# caretaker-easyvr.net
KiCad netlist of a schematic drawn in EAGLE
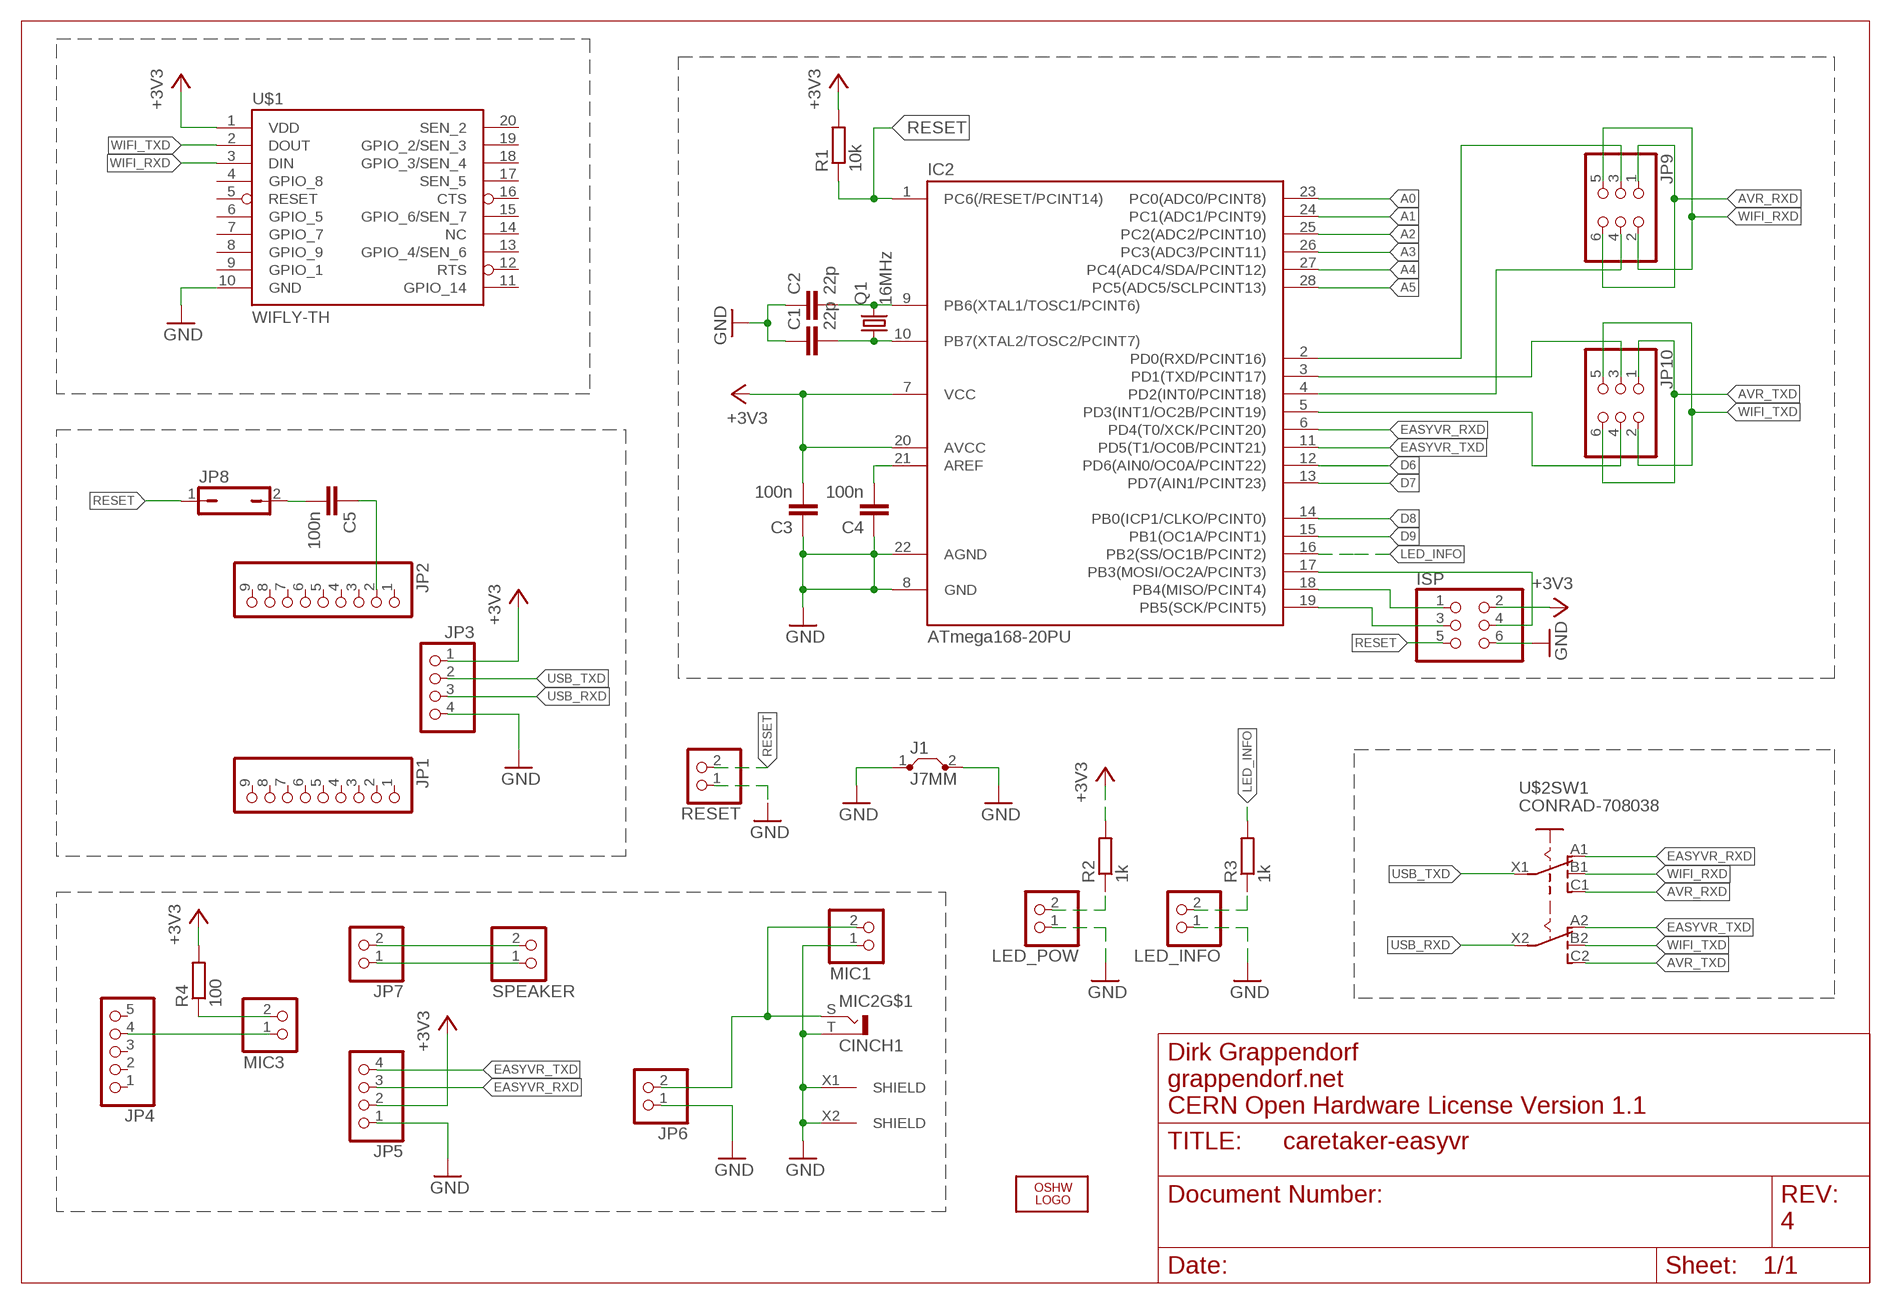
[diagram p0: schematic, sheet 1]

(export (version "E")
  (design (tool "Eeschema 10.0.6"))
  (components
    (comp (ref "C1")
      (value "22p")
      (footprint "eagle-import:C025-025X050")
      (libsource (lib "eagle-import") (part "C-EU025-025X050"))
    )
    (comp (ref "C2")
      (value "22p")
      (footprint "eagle-import:C025-025X050")
      (libsource (lib "eagle-import") (part "C-EU025-025X050"))
    )
    (comp (ref "C3")
      (value "100n")
      (footprint "eagle-import:C025-024X044")
      (libsource (lib "eagle-import") (part "C-EU025-024X044"))
    )
    (comp (ref "C4")
      (value "100n")
      (footprint "eagle-import:C025-024X044")
      (libsource (lib "eagle-import") (part "C-EU025-024X044"))
    )
    (comp (ref "C5")
      (value "100n")
      (footprint "eagle-import:C025-024X044")
      (libsource (lib "eagle-import") (part "C-EU025-024X044"))
    )
    (comp (ref "IC2")
      (value "ATmega168-20PU")
      (footprint "eagle-import:DIL28-3")
      (libsource (lib "eagle-import") (part "ATMEGA48/88/168-PU"))
    )
    (comp (ref "ISP")
      (value "PINHD-2X3")
      (footprint "eagle-import:2X03")
      (libsource (lib "eagle-import") (part "PINHD-2X3"))
    )
    (comp (ref "J1")
      (value "J7MM")
      (footprint "eagle-import:07")
      (libsource (lib "eagle-import") (part "J7MM"))
    )
    (comp (ref "JP1")
      (value "PINHD-1X9")
      (footprint "eagle-import:1X09")
      (libsource (lib "eagle-import") (part "PINHD-1X9"))
    )
    (comp (ref "JP2")
      (value "PINHD-1X9")
      (footprint "eagle-import:1X09")
      (libsource (lib "eagle-import") (part "PINHD-1X9"))
    )
    (comp (ref "JP3")
      (value "PINHD-1X4")
      (footprint "eagle-import:1X04")
      (libsource (lib "eagle-import") (part "PINHD-1X4"))
    )
    (comp (ref "JP4")
      (value "PINHD-1X5_2.00")
      (footprint "eagle-import:1X05M")
      (libsource (lib "eagle-import") (part "PINHD-1X5_2.00"))
    )
    (comp (ref "JP5")
      (value "PINHD-1X4_2.00")
      (footprint "eagle-import:1X04M")
      (libsource (lib "eagle-import") (part "PINHD-1X4_2.00"))
    )
    (comp (ref "JP6")
      (value "PINHD-1X2_2.00")
      (footprint "eagle-import:1X02M")
      (libsource (lib "eagle-import") (part "PINHD-1X2_2.00"))
    )
    (comp (ref "JP7")
      (value "PINHD-1X2_2.00")
      (footprint "eagle-import:1X02M")
      (libsource (lib "eagle-import") (part "PINHD-1X2_2.00"))
    )
    (comp (ref "JP8")
      (value "JP1Q")
      (footprint "eagle-import:JP1")
      (libsource (lib "eagle-import") (part "JP1Q"))
    )
    (comp (ref "JP9")
      (value "PINHD-2X3_2.54")
      (footprint "eagle-import:2X03")
      (libsource (lib "eagle-import") (part "PINHD-2X3_2.54"))
    )
    (comp (ref "JP10")
      (value "PINHD-2X3_2.54")
      (footprint "eagle-import:2X03")
      (libsource (lib "eagle-import") (part "PINHD-2X3_2.54"))
    )
    (comp (ref "LED_INFO")
      (value "PINHD-1X2_2.54")
      (footprint "eagle-import:1X02")
      (libsource (lib "eagle-import") (part "PINHD-1X2_2.54"))
    )
    (comp (ref "LED_POW")
      (value "PINHD-1X2_2.54")
      (footprint "eagle-import:1X02")
      (libsource (lib "eagle-import") (part "PINHD-1X2_2.54"))
    )
    (comp (ref "LOGO2")
      (value "OSHW_LOGO_10MILX0350-NT-BOTTOM")
      (footprint "eagle-import:OSHW_10X350_NOTEXT_BOTTOM")
      (libsource (lib "eagle-import") (part "OSHW_LOGO_10MILX0350-NT-BOTTOM"))
    )
    (comp (ref "MIC1")
      (value "PINHD-1X2_2.54")
      (footprint "eagle-import:1X02")
      (libsource (lib "eagle-import") (part "PINHD-1X2_2.54"))
    )
    (comp (ref "MIC2")
      (value "CINCH1")
      (footprint "eagle-import:CINCH1")
      (libsource (lib "eagle-import") (part "CINCH1"))
    )
    (comp (ref "MIC3")
      (value "PINHD-1X2_2.54")
      (footprint "eagle-import:1X02")
      (libsource (lib "eagle-import") (part "PINHD-1X2_2.54"))
    )
    (comp (ref "Q1")
      (value "16MHz")
      (footprint "eagle-import:HC49U-V")
      (libsource (lib "eagle-import") (part "CRYSTALHC49U-V"))
    )
    (comp (ref "R1")
      (value "10k")
      (footprint "eagle-import:0204_7")
      (libsource (lib "eagle-import") (part "R-EU_0204/7"))
    )
    (comp (ref "R2")
      (value "1k")
      (footprint "eagle-import:0204_7")
      (libsource (lib "eagle-import") (part "R-EU_0204/7"))
    )
    (comp (ref "R3")
      (value "1k")
      (footprint "eagle-import:0204_7")
      (libsource (lib "eagle-import") (part "R-EU_0204/7"))
    )
    (comp (ref "R4")
      (value "100")
      (footprint "eagle-import:0204_7")
      (libsource (lib "eagle-import") (part "R-EU_0204/7"))
    )
    (comp (ref "RESET")
      (value "PINHD-1X2_2.54")
      (footprint "eagle-import:1X02")
      (libsource (lib "eagle-import") (part "PINHD-1X2_2.54"))
    )
    (comp (ref "SPEAKER")
      (value "PINHD-1X2_2.54")
      (footprint "eagle-import:1X02")
      (libsource (lib "eagle-import") (part "PINHD-1X2_2.54"))
    )
    (comp (ref "U$1")
      (value "WIFLY-TH")
      (footprint "eagle-import:WIFLY-TH")
      (libsource (lib "eagle-import") (part "WIFLY-TH"))
    )
    (comp (ref "U$2")
      (value "CONRAD-708038")
      (footprint "eagle-import:CONRAD-708038")
      (libsource (lib "eagle-import") (part "CONRAD-708038"))
    )
  )
  (nets
    (net (code "1") (name "+3V3") (class "Default")
      (node (ref "C3") (pin "2") (pinfunction "2_2") (pintype "passive"))
      (node (ref "IC2") (pin "20") (pinfunction "AVCC_20") (pintype "passive"))
      (node (ref "IC2") (pin "7") (pinfunction "VCC_7") (pintype "power_in"))
      (node (ref "ISP") (pin "2") (pinfunction "2_2") (pintype "passive"))
      (node (ref "JP3") (pin "1") (pinfunction "1_1") (pintype "passive"))
      (node (ref "JP5") (pin "2") (pinfunction "2_2") (pintype "passive"))
      (node (ref "R1") (pin "2") (pinfunction "2_2") (pintype "passive"))
      (node (ref "R2") (pin "2") (pinfunction "2_2") (pintype "passive"))
      (node (ref "R4") (pin "2") (pinfunction "2_2") (pintype "passive"))
      (node (ref "U$1") (pin "1") (pinfunction "VDD_1") (pintype "power_in"))
    )
    (net (code "2") (name "A0") (class "Default")
      (node (ref "IC2") (pin "23") (pinfunction "PC0(ADC0/PCINT8)_23") (pintype "bidirectional"))
    )
    (net (code "3") (name "A1") (class "Default")
      (node (ref "IC2") (pin "24") (pinfunction "PC1(ADC1/PCINT9)_24") (pintype "bidirectional"))
    )
    (net (code "4") (name "A2") (class "Default")
      (node (ref "IC2") (pin "25") (pinfunction "PC2(ADC2/PCINT10)_25") (pintype "bidirectional"))
    )
    (net (code "5") (name "A3") (class "Default")
      (node (ref "IC2") (pin "26") (pinfunction "PC3(ADC3/PCINT11)_26") (pintype "bidirectional"))
    )
    (net (code "6") (name "A4") (class "Default")
      (node (ref "IC2") (pin "27") (pinfunction "PC4(ADC4/SDA/PCINT12)_27") (pintype "bidirectional"))
    )
    (net (code "7") (name "A5") (class "Default")
      (node (ref "IC2") (pin "28") (pinfunction "PC5(ADC5/SCLPCINT13)_28") (pintype "bidirectional"))
    )
    (net (code "8") (name "AVR_RXD") (class "Default")
      (node (ref "JP9") (pin "1") (pinfunction "1_1") (pintype "passive"))
      (node (ref "JP9") (pin "6") (pinfunction "6_6") (pintype "passive"))
      (node (ref "U$2") (pin "C1") (pinfunction "C1_C1") (pintype "bidirectional"))
    )
    (net (code "9") (name "AVR_TXD") (class "Default")
      (node (ref "JP10") (pin "1") (pinfunction "1_1") (pintype "passive"))
      (node (ref "JP10") (pin "6") (pinfunction "6_6") (pintype "passive"))
      (node (ref "U$2") (pin "C2") (pinfunction "C2_C2") (pintype "bidirectional"))
    )
    (net (code "10") (name "D6") (class "Default")
      (node (ref "IC2") (pin "12") (pinfunction "PD6(AIN0/OC0A/PCINT22)_12") (pintype "bidirectional"))
    )
    (net (code "11") (name "D7") (class "Default")
      (node (ref "IC2") (pin "13") (pinfunction "PD7(AIN1/PCINT23)_13") (pintype "bidirectional"))
    )
    (net (code "12") (name "D8") (class "Default")
      (node (ref "IC2") (pin "14") (pinfunction "PB0(ICP1/CLKO/PCINT0)_14") (pintype "bidirectional"))
    )
    (net (code "13") (name "D9") (class "Default")
      (node (ref "IC2") (pin "15") (pinfunction "PB1(OC1A/PCINT1)_15") (pintype "bidirectional"))
    )
    (net (code "14") (name "EASYVR_RXD") (class "Default")
      (node (ref "IC2") (pin "6") (pinfunction "PD4(T0/XCK/PCINT20)_6") (pintype "bidirectional"))
      (node (ref "JP5") (pin "3") (pinfunction "3_3") (pintype "passive"))
      (node (ref "U$2") (pin "A1") (pinfunction "A1_A1") (pintype "bidirectional"))
    )
    (net (code "15") (name "EASYVR_TXD") (class "Default")
      (node (ref "IC2") (pin "11") (pinfunction "PD5(T1/OC0B/PCINT21)_11") (pintype "bidirectional"))
      (node (ref "JP5") (pin "4") (pinfunction "4_4") (pintype "passive"))
      (node (ref "U$2") (pin "A2") (pinfunction "A2_A2") (pintype "bidirectional"))
    )
    (net (code "16") (name "GND") (class "Default")
      (node (ref "C1") (pin "1") (pinfunction "1_1") (pintype "passive"))
      (node (ref "C2") (pin "1") (pinfunction "1_1") (pintype "passive"))
      (node (ref "C3") (pin "1") (pinfunction "1_1") (pintype "passive"))
      (node (ref "C4") (pin "1") (pinfunction "1_1") (pintype "passive"))
      (node (ref "IC2") (pin "22") (pinfunction "AGND_22") (pintype "power_in"))
      (node (ref "IC2") (pin "8") (pinfunction "GND_8") (pintype "power_in"))
      (node (ref "ISP") (pin "6") (pinfunction "6_6") (pintype "passive"))
      (node (ref "J1") (pin "1") (pinfunction "1_1") (pintype "passive"))
      (node (ref "J1") (pin "2") (pinfunction "2_2") (pintype "passive"))
      (node (ref "JP3") (pin "4") (pinfunction "4_4") (pintype "passive"))
      (node (ref "JP5") (pin "1") (pinfunction "1_1") (pintype "passive"))
      (node (ref "JP6") (pin "1") (pinfunction "1_1") (pintype "passive"))
      (node (ref "LED_INFO") (pin "1") (pinfunction "1_1") (pintype "passive"))
      (node (ref "LED_POW") (pin "1") (pinfunction "1_1") (pintype "passive"))
      (node (ref "MIC1") (pin "1") (pinfunction "1_1") (pintype "passive"))
      (node (ref "MIC2") (pin "T") (pinfunction "T_T") (pintype "passive"))
      (node (ref "MIC2") (pin "X1") (pinfunction "SHIELD_X1") (pintype "power_in"))
      (node (ref "MIC2") (pin "X2") (pinfunction "SHIELD_X2") (pintype "power_in"))
      (node (ref "RESET") (pin "1") (pinfunction "1_1") (pintype "passive"))
      (node (ref "U$1") (pin "10") (pinfunction "GND_10") (pintype "power_in"))
    )
    (net (code "17") (name "LED_INFO") (class "Default")
      (node (ref "IC2") (pin "16") (pinfunction "PB2(SS/OC1B/PCINT2)_16") (pintype "bidirectional"))
      (node (ref "R3") (pin "2") (pinfunction "2_2") (pintype "passive"))
    )
    (net (code "18") (name "Net-(C5-Pad1)") (class "Default")
      (node (ref "C5") (pin "1") (pinfunction "1_1") (pintype "passive"))
      (node (ref "JP2") (pin "2") (pinfunction "2_2") (pintype "passive"))
    )
    (net (code "19") (name "Net-(C5-Pad2)") (class "Default")
      (node (ref "C5") (pin "2") (pinfunction "2_2") (pintype "passive"))
      (node (ref "JP8") (pin "2") (pinfunction "2_2") (pintype "passive"))
    )
    (net (code "20") (name "Net-(IC2-AREF)") (class "Default")
      (node (ref "C4") (pin "2") (pinfunction "2_2") (pintype "passive"))
      (node (ref "IC2") (pin "21") (pinfunction "AREF_21") (pintype "passive"))
    )
    (net (code "21") (name "Net-(IC2-PB3(MOSI{slash}OC2A{slash}PCINT3))") (class "Default")
      (node (ref "IC2") (pin "17") (pinfunction "PB3(MOSI/OC2A/PCINT3)_17") (pintype "bidirectional"))
      (node (ref "ISP") (pin "4") (pinfunction "4_4") (pintype "passive"))
    )
    (net (code "22") (name "Net-(IC2-PB4(MISO{slash}PCINT4))") (class "Default")
      (node (ref "IC2") (pin "18") (pinfunction "PB4(MISO/PCINT4)_18") (pintype "bidirectional"))
      (node (ref "ISP") (pin "1") (pinfunction "1_1") (pintype "passive"))
    )
    (net (code "23") (name "Net-(IC2-PB5(SCK{slash}PCINT5))") (class "Default")
      (node (ref "IC2") (pin "19") (pinfunction "PB5(SCK/PCINT5)_19") (pintype "bidirectional"))
      (node (ref "ISP") (pin "3") (pinfunction "3_3") (pintype "passive"))
    )
    (net (code "24") (name "Net-(IC2-PB6(XTAL1{slash}TOSC1{slash}PCINT6))") (class "Default")
      (node (ref "C2") (pin "2") (pinfunction "2_2") (pintype "passive"))
      (node (ref "IC2") (pin "9") (pinfunction "PB6(XTAL1/TOSC1/PCINT6)_9") (pintype "bidirectional"))
      (node (ref "Q1") (pin "2") (pinfunction "2_2") (pintype "passive"))
    )
    (net (code "25") (name "Net-(IC2-PB7(XTAL2{slash}TOSC2{slash}PCINT7))") (class "Default")
      (node (ref "C1") (pin "2") (pinfunction "2_2") (pintype "passive"))
      (node (ref "IC2") (pin "10") (pinfunction "PB7(XTAL2/TOSC2/PCINT7)_10") (pintype "bidirectional"))
      (node (ref "Q1") (pin "1") (pinfunction "1_1") (pintype "passive"))
    )
    (net (code "26") (name "Net-(IC2-PD0(RXD{slash}PCINT16))") (class "Default")
      (node (ref "IC2") (pin "2") (pinfunction "PD0(RXD/PCINT16)_2") (pintype "bidirectional"))
      (node (ref "JP9") (pin "3") (pinfunction "3_3") (pintype "passive"))
    )
    (net (code "27") (name "Net-(IC2-PD1(TXD{slash}PCINT17))") (class "Default")
      (node (ref "IC2") (pin "3") (pinfunction "PD1(TXD/PCINT17)_3") (pintype "bidirectional"))
      (node (ref "JP10") (pin "3") (pinfunction "3_3") (pintype "passive"))
    )
    (net (code "28") (name "Net-(IC2-PD2(INT0{slash}PCINT18))") (class "Default")
      (node (ref "IC2") (pin "4") (pinfunction "PD2(INT0/PCINT18)_4") (pintype "bidirectional"))
      (node (ref "JP9") (pin "4") (pinfunction "4_4") (pintype "passive"))
    )
    (net (code "29") (name "Net-(IC2-PD3(INT1{slash}OC2B{slash}PCINT19))") (class "Default")
      (node (ref "IC2") (pin "5") (pinfunction "PD3(INT1/OC2B/PCINT19)_5") (pintype "bidirectional"))
      (node (ref "JP10") (pin "4") (pinfunction "4_4") (pintype "passive"))
    )
    (net (code "30") (name "Net-(JP4-Pad4)") (class "Default")
      (node (ref "JP4") (pin "4") (pinfunction "4_4") (pintype "passive"))
      (node (ref "MIC3") (pin "1") (pinfunction "1_1") (pintype "passive"))
    )
    (net (code "31") (name "Net-(JP6-Pad2)") (class "Default")
      (node (ref "JP6") (pin "2") (pinfunction "2_2") (pintype "passive"))
      (node (ref "MIC1") (pin "2") (pinfunction "2_2") (pintype "passive"))
      (node (ref "MIC2") (pin "S") (pinfunction "S_S") (pintype "passive"))
    )
    (net (code "32") (name "Net-(JP7-Pad1)") (class "Default")
      (node (ref "JP7") (pin "1") (pinfunction "1_1") (pintype "passive"))
      (node (ref "SPEAKER") (pin "1") (pinfunction "1_1") (pintype "passive"))
    )
    (net (code "33") (name "Net-(JP7-Pad2)") (class "Default")
      (node (ref "JP7") (pin "2") (pinfunction "2_2") (pintype "passive"))
      (node (ref "SPEAKER") (pin "2") (pinfunction "2_2") (pintype "passive"))
    )
    (net (code "34") (name "Net-(LED_INFO-Pad2)") (class "Default")
      (node (ref "LED_INFO") (pin "2") (pinfunction "2_2") (pintype "passive"))
      (node (ref "R3") (pin "1") (pinfunction "1_1") (pintype "passive"))
    )
    (net (code "35") (name "Net-(LED_POW-Pad2)") (class "Default")
      (node (ref "LED_POW") (pin "2") (pinfunction "2_2") (pintype "passive"))
      (node (ref "R2") (pin "1") (pinfunction "1_1") (pintype "passive"))
    )
    (net (code "36") (name "Net-(MIC3-Pad2)") (class "Default")
      (node (ref "MIC3") (pin "2") (pinfunction "2_2") (pintype "passive"))
      (node (ref "R4") (pin "1") (pinfunction "1_1") (pintype "passive"))
    )
    (net (code "37") (name "RESET") (class "Default")
      (node (ref "IC2") (pin "1") (pinfunction "PC6(/RESET/PCINT14)_1") (pintype "bidirectional"))
      (node (ref "ISP") (pin "5") (pinfunction "5_5") (pintype "passive"))
      (node (ref "JP8") (pin "1") (pinfunction "1_1") (pintype "passive"))
      (node (ref "R1") (pin "1") (pinfunction "1_1") (pintype "passive"))
      (node (ref "RESET") (pin "2") (pinfunction "2_2") (pintype "passive"))
    )
    (net (code "38") (name "USB_RXD") (class "Default")
      (node (ref "JP3") (pin "3") (pinfunction "3_3") (pintype "passive"))
      (node (ref "U$2") (pin "X2") (pinfunction "X2_X2") (pintype "bidirectional"))
    )
    (net (code "39") (name "USB_TXD") (class "Default")
      (node (ref "JP3") (pin "2") (pinfunction "2_2") (pintype "passive"))
      (node (ref "U$2") (pin "X1") (pinfunction "X1_X1") (pintype "bidirectional"))
    )
    (net (code "40") (name "WIFI_RXD") (class "Default")
      (node (ref "JP9") (pin "2") (pinfunction "2_2") (pintype "passive"))
      (node (ref "JP9") (pin "5") (pinfunction "5_5") (pintype "passive"))
      (node (ref "U$1") (pin "3") (pinfunction "DIN_3") (pintype "input"))
      (node (ref "U$2") (pin "B1") (pinfunction "B1_B1") (pintype "bidirectional"))
    )
    (net (code "41") (name "WIFI_TXD") (class "Default")
      (node (ref "JP10") (pin "2") (pinfunction "2_2") (pintype "passive"))
      (node (ref "JP10") (pin "5") (pinfunction "5_5") (pintype "passive"))
      (node (ref "U$1") (pin "2") (pinfunction "DOUT_2") (pintype "output"))
      (node (ref "U$2") (pin "B2") (pinfunction "B2_B2") (pintype "bidirectional"))
    )
    (net (code "42") (name "unconnected-(JP1-Pad1)") (class "Default")
      (node (ref "JP1") (pin "1") (pinfunction "1_1") (pintype "passive"))
    )
    (net (code "43") (name "unconnected-(JP1-Pad2)") (class "Default")
      (node (ref "JP1") (pin "2") (pinfunction "2_2") (pintype "passive"))
    )
    (net (code "44") (name "unconnected-(JP1-Pad3)") (class "Default")
      (node (ref "JP1") (pin "3") (pinfunction "3_3") (pintype "passive"))
    )
    (net (code "45") (name "unconnected-(JP1-Pad4)") (class "Default")
      (node (ref "JP1") (pin "4") (pinfunction "4_4") (pintype "passive"))
    )
    (net (code "46") (name "unconnected-(JP1-Pad5)") (class "Default")
      (node (ref "JP1") (pin "5") (pinfunction "5_5") (pintype "passive"))
    )
    (net (code "47") (name "unconnected-(JP1-Pad6)") (class "Default")
      (node (ref "JP1") (pin "6") (pinfunction "6_6") (pintype "passive"))
    )
    (net (code "48") (name "unconnected-(JP1-Pad7)") (class "Default")
      (node (ref "JP1") (pin "7") (pinfunction "7_7") (pintype "passive"))
    )
    (net (code "49") (name "unconnected-(JP1-Pad8)") (class "Default")
      (node (ref "JP1") (pin "8") (pinfunction "8_8") (pintype "passive"))
    )
    (net (code "50") (name "unconnected-(JP1-Pad9)") (class "Default")
      (node (ref "JP1") (pin "9") (pinfunction "9_9") (pintype "passive"))
    )
    (net (code "51") (name "unconnected-(JP2-Pad1)") (class "Default")
      (node (ref "JP2") (pin "1") (pinfunction "1_1") (pintype "passive"))
    )
    (net (code "52") (name "unconnected-(JP2-Pad3)") (class "Default")
      (node (ref "JP2") (pin "3") (pinfunction "3_3") (pintype "passive"))
    )
    (net (code "53") (name "unconnected-(JP2-Pad4)") (class "Default")
      (node (ref "JP2") (pin "4") (pinfunction "4_4") (pintype "passive"))
    )
    (net (code "54") (name "unconnected-(JP2-Pad5)") (class "Default")
      (node (ref "JP2") (pin "5") (pinfunction "5_5") (pintype "passive"))
    )
    (net (code "55") (name "unconnected-(JP2-Pad6)") (class "Default")
      (node (ref "JP2") (pin "6") (pinfunction "6_6") (pintype "passive"))
    )
    (net (code "56") (name "unconnected-(JP2-Pad7)") (class "Default")
      (node (ref "JP2") (pin "7") (pinfunction "7_7") (pintype "passive"))
    )
    (net (code "57") (name "unconnected-(JP2-Pad8)") (class "Default")
      (node (ref "JP2") (pin "8") (pinfunction "8_8") (pintype "passive"))
    )
    (net (code "58") (name "unconnected-(JP2-Pad9)") (class "Default")
      (node (ref "JP2") (pin "9") (pinfunction "9_9") (pintype "passive"))
    )
    (net (code "59") (name "unconnected-(JP4-Pad1)") (class "Default")
      (node (ref "JP4") (pin "1") (pinfunction "1_1") (pintype "passive"))
    )
    (net (code "60") (name "unconnected-(JP4-Pad2)") (class "Default")
      (node (ref "JP4") (pin "2") (pinfunction "2_2") (pintype "passive"))
    )
    (net (code "61") (name "unconnected-(JP4-Pad3)") (class "Default")
      (node (ref "JP4") (pin "3") (pinfunction "3_3") (pintype "passive"))
    )
    (net (code "62") (name "unconnected-(JP4-Pad5)") (class "Default")
      (node (ref "JP4") (pin "5") (pinfunction "5_5") (pintype "passive"))
    )
    (net (code "63") (name "unconnected-(U$1-CTS-Pad16)") (class "Default")
      (node (ref "U$1") (pin "16") (pinfunction "CTS_16") (pintype "input"))
    )
    (net (code "64") (name "unconnected-(U$1-GPIO_1-Pad9)") (class "Default")
      (node (ref "U$1") (pin "9") (pinfunction "GPIO_1_9") (pintype "bidirectional"))
    )
    (net (code "65") (name "unconnected-(U$1-GPIO_2{slash}SEN_3-Pad19)") (class "Default")
      (node (ref "U$1") (pin "19") (pinfunction "GPIO_2/SEN_3_19") (pintype "bidirectional"))
    )
    (net (code "66") (name "unconnected-(U$1-GPIO_3{slash}SEN_4-Pad18)") (class "Default")
      (node (ref "U$1") (pin "18") (pinfunction "GPIO_3/SEN_4_18") (pintype "bidirectional"))
    )
    (net (code "67") (name "unconnected-(U$1-GPIO_4{slash}SEN_6-Pad13)") (class "Default")
      (node (ref "U$1") (pin "13") (pinfunction "GPIO_4/SEN_6_13") (pintype "bidirectional"))
    )
    (net (code "68") (name "unconnected-(U$1-GPIO_5-Pad6)") (class "Default")
      (node (ref "U$1") (pin "6") (pinfunction "GPIO_5_6") (pintype "bidirectional"))
    )
    (net (code "69") (name "unconnected-(U$1-GPIO_6{slash}SEN_7-Pad15)") (class "Default")
      (node (ref "U$1") (pin "15") (pinfunction "GPIO_6/SEN_7_15") (pintype "bidirectional"))
    )
    (net (code "70") (name "unconnected-(U$1-GPIO_7-Pad7)") (class "Default")
      (node (ref "U$1") (pin "7") (pinfunction "GPIO_7_7") (pintype "bidirectional"))
    )
    (net (code "71") (name "unconnected-(U$1-GPIO_8-Pad4)") (class "Default")
      (node (ref "U$1") (pin "4") (pinfunction "GPIO_8_4") (pintype "bidirectional"))
    )
    (net (code "72") (name "unconnected-(U$1-GPIO_9-Pad8)") (class "Default")
      (node (ref "U$1") (pin "8") (pinfunction "GPIO_9_8") (pintype "bidirectional"))
    )
    (net (code "73") (name "unconnected-(U$1-GPIO_14-Pad11)") (class "Default")
      (node (ref "U$1") (pin "11") (pinfunction "GPIO_14_11") (pintype "bidirectional"))
    )
    (net (code "74") (name "unconnected-(U$1-NC-Pad14)") (class "Default")
      (node (ref "U$1") (pin "14") (pinfunction "NC_14") (pintype "bidirectional"))
    )
    (net (code "75") (name "unconnected-(U$1-RESET-Pad5)") (class "Default")
      (node (ref "U$1") (pin "5") (pinfunction "RESET_5") (pintype "input"))
    )
    (net (code "76") (name "unconnected-(U$1-RTS-Pad12)") (class "Default")
      (node (ref "U$1") (pin "12") (pinfunction "RTS_12") (pintype "output"))
    )
    (net (code "77") (name "unconnected-(U$1-SEN_2-Pad20)") (class "Default")
      (node (ref "U$1") (pin "20") (pinfunction "SEN_2_20") (pintype "bidirectional"))
    )
    (net (code "78") (name "unconnected-(U$1-SEN_5-Pad17)") (class "Default")
      (node (ref "U$1") (pin "17") (pinfunction "SEN_5_17") (pintype "bidirectional"))
    )
  )
)
